# DM1097_BootSel.net
KiCad netlist of a schematic drawn in Altium Designer
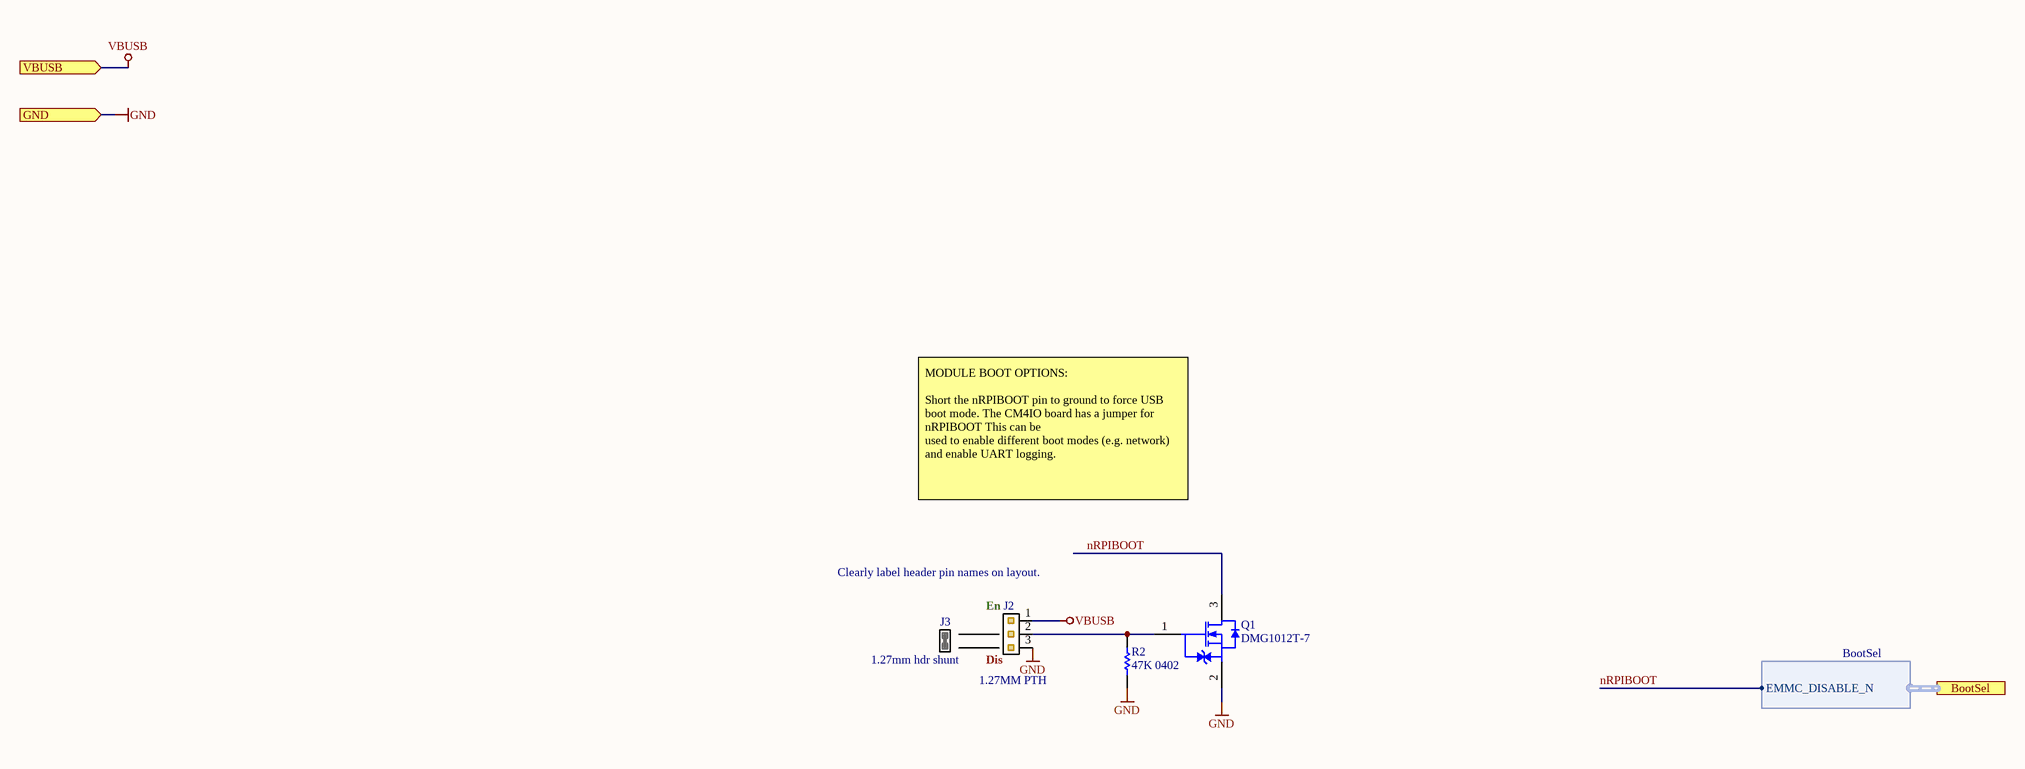
[diagram p0: DM1097_BootSel.SchDoc]

(export (version "E")
  (design (tool "Eeschema 10.0.6"))
  (components
    (comp (ref "J2")
      (value "1.27MM PTH")
      (footprint "GRPB031VWVN-RC")
      (description "CONN HEADER VERT 3POS 1.27MM")
      (libsource (lib "LuxonisMaster") (part "GRPB031VWVN-RC"))
    )
    (comp (ref "J3")
      (value "1.27mm hdr shunt")
      (footprint "M50-1900005")
      (description "CONN SHUNT 1.27MM BLACK")
      (libsource (lib "LuxonisMaster") (part "M50-1900005"))
    )
    (comp (ref "Q1")
      (value "DMG1012T-7")
      (footprint "DMG1012T-7")
      (description "MOSFET N-CH 20V 630MA SOT-523")
      (libsource (lib "LuxonisMaster") (part "DMG1012T-7"))
    )
    (comp (ref "R2")
      (value "47K 0402")
      (footprint "RESC0402(1005)_N")
      (description "RES SMD 47K OHM 1% 1/16W 0402")
      (fields (field (name "TOLERANCE") "1%"))
      (libsource (lib "LuxonisMaster") (part "RC0402FR-0747KL"))
    )
  )
  (nets
    (net (code "2") (name "/nRPIBOOT") (class "Default")
      (node (ref "Q1") (pin "3") (pinfunction "3_3") (pintype "passive"))
    )
    (net (code "4") (name "GND") (class "Default")
      (node (ref "J2") (pin "3") (pinfunction "3_3") (pintype "passive"))
      (node (ref "Q1") (pin "2") (pinfunction "2_2") (pintype "passive"))
      (node (ref "R2") (pin "1") (pinfunction "1_1") (pintype "passive"))
    )
    (net (code "5") (name "Net-(J2-Pad2)") (class "Default")
      (node (ref "J2") (pin "2") (pinfunction "2_2") (pintype "passive"))
      (node (ref "Q1") (pin "1") (pinfunction "1_1") (pintype "passive"))
      (node (ref "R2") (pin "2") (pinfunction "2_2") (pintype "passive"))
    )
    (net (code "6") (name "VBUSB") (class "Default")
      (node (ref "J2") (pin "1") (pinfunction "1_1") (pintype "passive"))
    )
  )
)
